# extension_card.net
KiCad netlist of a schematic drawn in Altium Designer
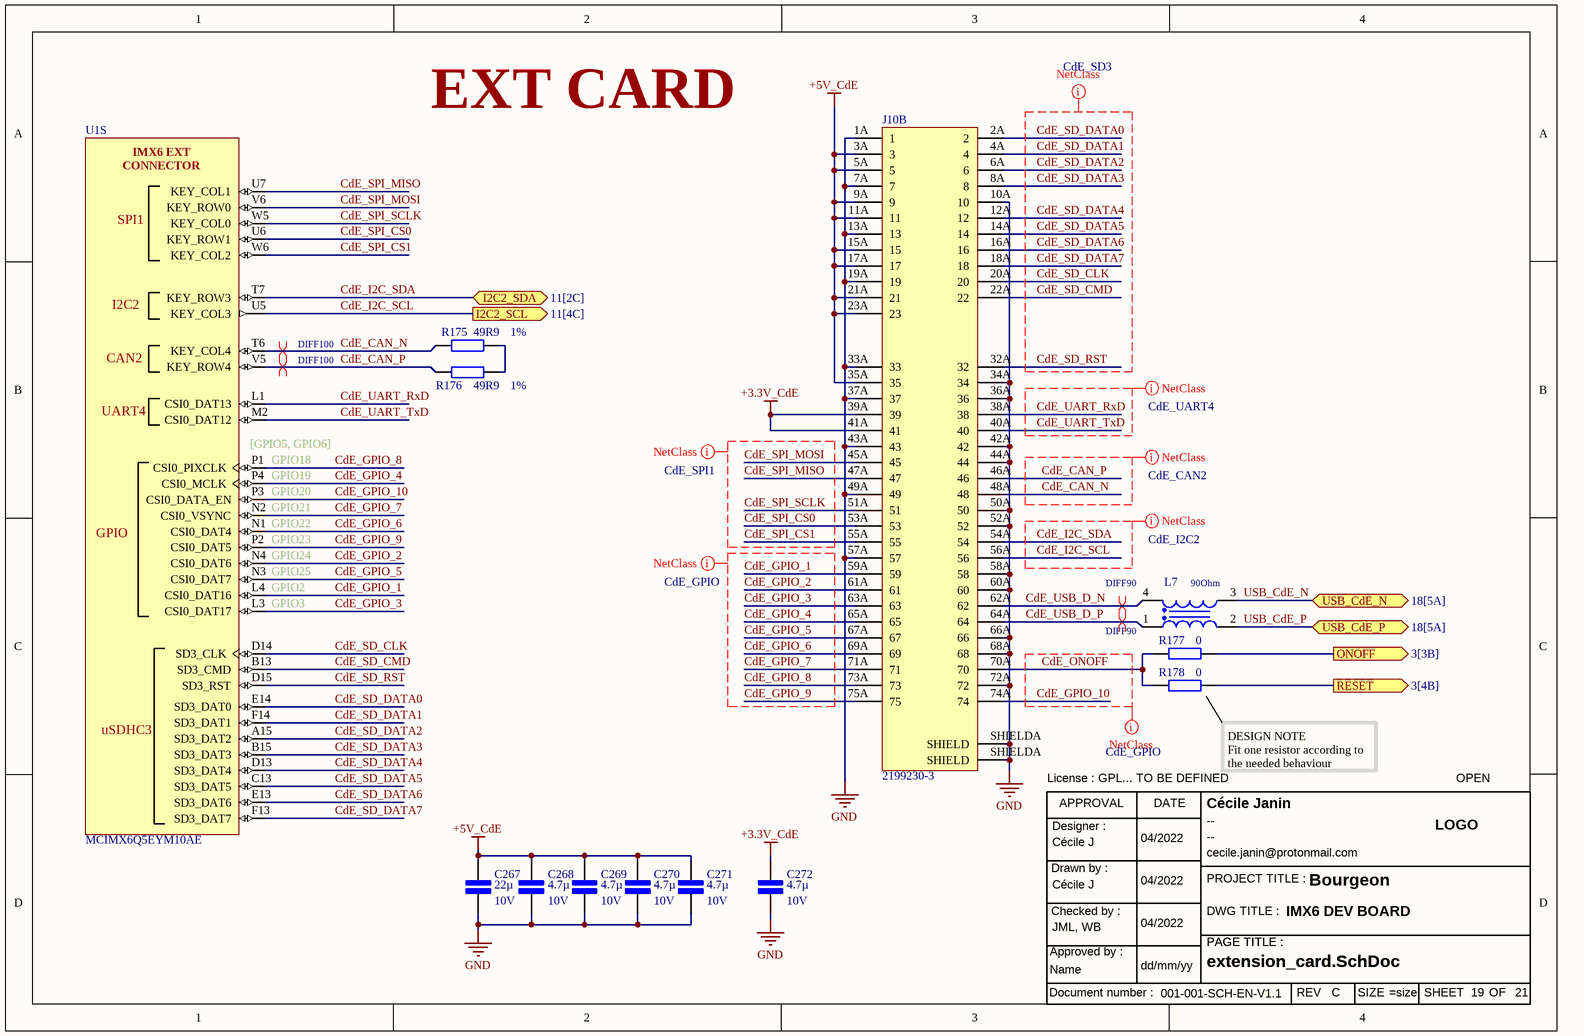
[diagram p0: extension_card.SchDoc]

(export (version "E")
  (design (tool "Eeschema 10.0.6"))
  (components
    (comp (ref "C267")
      (value "22µ")
      (footprint "Cap cer 0603/4608")
      (description "cap cer 22µ 10V 10% X5R 0603")
      (fields (field (name "TENSION DU DIÉLECTRIQUE") "10V"))
      (libsource (lib "First Board IMX6") (part "cap 22µ 10V"))
    )
    (comp (ref "C268")
      (value "4.7µ")
      (footprint "Cap cer 0402/1005")
      (description "cap cer 4.7µ 10V 10% X7R 0402")
      (fields (field (name "TENSION DU DIÉLECTRIQUE") "10V"))
      (libsource (lib "First Board IMX6") (part "cap 4.7µ 10V"))
    )
    (comp (ref "C269")
      (value "4.7µ")
      (footprint "Cap cer 0402/1005")
      (description "cap cer 4.7µ 10V 10% X7R 0402")
      (fields (field (name "TENSION DU DIÉLECTRIQUE") "10V"))
      (libsource (lib "First Board IMX6") (part "cap 4.7µ 10V"))
    )
    (comp (ref "C270")
      (value "4.7µ")
      (footprint "Cap cer 0402/1005")
      (description "cap cer 4.7µ 10V 10% X7R 0402")
      (fields (field (name "TENSION DU DIÉLECTRIQUE") "10V"))
      (libsource (lib "First Board IMX6") (part "cap 4.7µ 10V"))
    )
    (comp (ref "C271")
      (value "4.7µ")
      (footprint "Cap cer 0402/1005")
      (description "cap cer 4.7µ 10V 10% X7R 0402")
      (fields (field (name "TENSION DU DIÉLECTRIQUE") "10V"))
      (libsource (lib "First Board IMX6") (part "cap 4.7µ 10V"))
    )
    (comp (ref "C272")
      (value "4.7µ")
      (footprint "Cap cer 0402/1005")
      (description "cap cer 4.7µ 10V 10% X7R 0402")
      (fields (field (name "TENSION DU DIÉLECTRIQUE") "10V"))
      (libsource (lib "First Board IMX6") (part "cap 4.7µ 10V"))
    )
    (comp (ref "J10")
      (value "2199230-3")
      (footprint "SATA_M2_ 2199230-3")
      (libsource (lib "First Board IMX6") (part "SATA_M.2_2199230-3 / multi interface"))
    )
    (comp (ref "L7")
      (value "90Ohm")
      (footprint "inductor coupled usb 0603")
      (description "WE-CNSW SMT Common Mode Line Filter, size 0603, 90Ohm, 0.55A, 50V")
      (fields
        (field (name "MANUFACTURER PART NUMBER") "744230900")
        (field (name "MANUFACTURER") "Wurth Elektronik")
      )
      (libsource (lib "First Board IMX6") (part "inductor coupled USB"))
    )
    (comp (ref "R175")
      (value "49R9")
      (footprint "Res 0402/1005")
      (description "res 49R9 ohm 1% 0402")
      (fields (field (name "POURCENTAGE") "1%"))
      (libsource (lib "First Board IMX6") (part "res 49R9 1%"))
    )
    (comp (ref "R176")
      (value "49R9")
      (footprint "Res 0402/1005")
      (description "res 49R9 ohm 1% 0402")
      (fields (field (name "POURCENTAGE") "1%"))
      (libsource (lib "First Board IMX6") (part "res 49R9 1%"))
    )
    (comp (ref "R177")
      (value "0")
      (footprint "Res 0603/1603")
      (description "res 0603")
      (libsource (lib "First Board IMX6") (part "res 0Ohm"))
    )
    (comp (ref "R178")
      (value "0")
      (footprint "Res 0603/1603")
      (description "res 0603")
      (libsource (lib "First Board IMX6") (part "res 0Ohm"))
    )
    (comp (ref "TB18")
      (value "Title bloc ANSI modified")
      (libsource (lib "First Board IMX6") (part "Title bloc ANSI"))
    )
    (comp (ref "U1")
      (value "MCIMX6Q5EYM10AE")
      (footprint "FRES-2197-01")
      (fields
        (field (name "PARTNUMBER") "MCIMX6Q5EYM10ACR")
        (field (name "MANUFACTURER") "Freescale Semiconductor")
      )
      (libsource (lib "First Board IMX6") (part "IMX6Q5EYM10AE"))
    )
  )
  (nets
    (net (code "1") (name "+3.3V_CdE") (class "Default")
      (node (ref "C272") (pin "1") (pinfunction "3_1") (pintype "passive"))
      (node (ref "J10") (pin "39A") (pinfunction "39_39A") (pintype "passive"))
      (node (ref "J10") (pin "41A") (pinfunction "41_41A") (pintype "passive"))
    )
    (net (code "2") (name "+5V_CdE") (class "Default")
      (node (ref "C267") (pin "1") (pinfunction "3_1") (pintype "passive"))
      (node (ref "C268") (pin "1") (pinfunction "3_1") (pintype "passive"))
      (node (ref "C269") (pin "1") (pinfunction "3_1") (pintype "passive"))
      (node (ref "C270") (pin "1") (pinfunction "3_1") (pintype "passive"))
      (node (ref "C271") (pin "1") (pinfunction "3_1") (pintype "passive"))
      (node (ref "J10") (pin "11A") (pinfunction "11_11A") (pintype "passive"))
      (node (ref "J10") (pin "15A") (pinfunction "15_15A") (pintype "passive"))
      (node (ref "J10") (pin "17A") (pinfunction "17_17A") (pintype "passive"))
      (node (ref "J10") (pin "21A") (pinfunction "21_21A") (pintype "passive"))
      (node (ref "J10") (pin "23A") (pinfunction "23_23A") (pintype "passive"))
      (node (ref "J10") (pin "35A") (pinfunction "35_35A") (pintype "passive"))
      (node (ref "J10") (pin "3A") (pinfunction "3_3A") (pintype "passive"))
      (node (ref "J10") (pin "5A") (pinfunction "5_5A") (pintype "passive"))
      (node (ref "J10") (pin "9A") (pinfunction "9_9A") (pintype "passive"))
    )
    (net (code "3") (name "/CdE_CAN_N") (class "Default")
      (node (ref "J10") (pin "48A") (pinfunction "48_48A") (pintype "passive"))
      (node (ref "R175") (pin "2") (pintype "passive"))
      (node (ref "U1") (pin "T6") (pinfunction "KEY_COL4_T6") (pintype "bidirectional"))
    )
    (net (code "4") (name "/CdE_CAN_P") (class "Default")
      (node (ref "J10") (pin "46A") (pinfunction "46_46A") (pintype "passive"))
      (node (ref "R176") (pin "2") (pintype "passive"))
      (node (ref "U1") (pin "V5") (pinfunction "KEY_ROW4_V5") (pintype "bidirectional"))
    )
    (net (code "5") (name "/CdE_GPIO_1") (class "Default")
      (node (ref "J10") (pin "59A") (pinfunction "59_59A") (pintype "passive"))
      (node (ref "U1") (pin "L4") (pinfunction "CSI0_DAT16_L4") (pintype "bidirectional"))
    )
    (net (code "6") (name "/CdE_GPIO_2") (class "Default")
      (node (ref "J10") (pin "61A") (pinfunction "61_61A") (pintype "passive"))
      (node (ref "U1") (pin "N4") (pinfunction "CSI0_DAT6_N4") (pintype "bidirectional"))
    )
    (net (code "7") (name "/CdE_GPIO_3") (class "Default")
      (node (ref "J10") (pin "63A") (pinfunction "63_63A") (pintype "passive"))
      (node (ref "U1") (pin "L3") (pinfunction "CSI0_DAT17_L3") (pintype "bidirectional"))
    )
    (net (code "8") (name "/CdE_GPIO_4") (class "Default")
      (node (ref "J10") (pin "65A") (pinfunction "65_65A") (pintype "passive"))
      (node (ref "U1") (pin "P4") (pinfunction "CSI0_MCLK_P4") (pintype "bidirectional"))
    )
    (net (code "9") (name "/CdE_GPIO_5") (class "Default")
      (node (ref "J10") (pin "67A") (pinfunction "67_67A") (pintype "passive"))
      (node (ref "U1") (pin "N3") (pinfunction "CSI0_DAT7_N3") (pintype "bidirectional"))
    )
    (net (code "10") (name "/CdE_GPIO_6") (class "Default")
      (node (ref "J10") (pin "69A") (pinfunction "69_69A") (pintype "passive"))
      (node (ref "U1") (pin "N1") (pinfunction "CSI0_DAT4_N1") (pintype "bidirectional"))
    )
    (net (code "11") (name "/CdE_GPIO_7") (class "Default")
      (node (ref "J10") (pin "71A") (pinfunction "71_71A") (pintype "passive"))
      (node (ref "U1") (pin "N2") (pinfunction "CSI0_VSYNC_N2") (pintype "bidirectional"))
    )
    (net (code "12") (name "/CdE_GPIO_8") (class "Default")
      (node (ref "J10") (pin "73A") (pinfunction "73_73A") (pintype "passive"))
      (node (ref "U1") (pin "P1") (pinfunction "CSI0_PIXCLK_P1") (pintype "bidirectional"))
    )
    (net (code "13") (name "/CdE_GPIO_9") (class "Default")
      (node (ref "J10") (pin "75A") (pinfunction "75_75A") (pintype "passive"))
      (node (ref "U1") (pin "P2") (pinfunction "CSI0_DAT5_P2") (pintype "bidirectional"))
    )
    (net (code "14") (name "/CdE_GPIO_10") (class "Default")
      (node (ref "J10") (pin "74A") (pinfunction "74_74A") (pintype "passive"))
      (node (ref "U1") (pin "P3") (pinfunction "CSI0_DATA_EN_P3") (pintype "bidirectional"))
    )
    (net (code "15") (name "/CdE_I2C_SCL") (class "Default")
      (node (ref "J10") (pin "56A") (pinfunction "56_56A") (pintype "passive"))
      (node (ref "U1") (pin "U5") (pinfunction "KEY_COL3_U5") (pintype "output"))
    )
    (net (code "16") (name "/CdE_I2C_SDA") (class "Default")
      (node (ref "J10") (pin "54A") (pinfunction "54_54A") (pintype "passive"))
      (node (ref "U1") (pin "T7") (pinfunction "KEY_ROW3_T7") (pintype "bidirectional"))
    )
    (net (code "17") (name "/CdE_ONOFF") (class "Default")
      (node (ref "J10") (pin "70A") (pinfunction "70_70A") (pintype "passive"))
      (node (ref "R177") (pin "1") (pintype "passive"))
      (node (ref "R178") (pin "1") (pintype "passive"))
    )
    (net (code "18") (name "/CdE_SD_CLK") (class "Default")
      (node (ref "J10") (pin "20A") (pinfunction "20_20A") (pintype "passive"))
      (node (ref "U1") (pin "D14") (pinfunction "SD3_CLK_D14") (pintype "bidirectional"))
    )
    (net (code "19") (name "/CdE_SD_CMD") (class "Default")
      (node (ref "J10") (pin "22A") (pinfunction "22_22A") (pintype "passive"))
      (node (ref "U1") (pin "B13") (pinfunction "SD3_CMD_B13") (pintype "bidirectional"))
    )
    (net (code "20") (name "/CdE_SD_DATA0") (class "Default")
      (node (ref "J10") (pin "2A") (pinfunction "2_2A") (pintype "passive"))
      (node (ref "U1") (pin "E14") (pinfunction "SD3_DAT0_E14") (pintype "bidirectional"))
    )
    (net (code "21") (name "/CdE_SD_DATA1") (class "Default")
      (node (ref "J10") (pin "4A") (pinfunction "4_4A") (pintype "passive"))
      (node (ref "U1") (pin "F14") (pinfunction "SD3_DAT1_F14") (pintype "bidirectional"))
    )
    (net (code "22") (name "/CdE_SD_DATA2") (class "Default")
      (node (ref "J10") (pin "6A") (pinfunction "6_6A") (pintype "passive"))
      (node (ref "U1") (pin "A15") (pinfunction "SD3_DAT2_A15") (pintype "bidirectional"))
    )
    (net (code "23") (name "/CdE_SD_DATA3") (class "Default")
      (node (ref "J10") (pin "8A") (pinfunction "8_8A") (pintype "passive"))
      (node (ref "U1") (pin "B15") (pinfunction "SD3_DAT3_B15") (pintype "bidirectional"))
    )
    (net (code "24") (name "/CdE_SD_DATA4") (class "Default")
      (node (ref "J10") (pin "12A") (pinfunction "12_12A") (pintype "passive"))
      (node (ref "U1") (pin "D13") (pinfunction "SD3_DAT4_D13") (pintype "bidirectional"))
    )
    (net (code "25") (name "/CdE_SD_DATA5") (class "Default")
      (node (ref "J10") (pin "14A") (pinfunction "14_14A") (pintype "passive"))
      (node (ref "U1") (pin "C13") (pinfunction "SD3_DAT5_C13") (pintype "bidirectional"))
    )
    (net (code "26") (name "/CdE_SD_DATA6") (class "Default")
      (node (ref "J10") (pin "16A") (pinfunction "16_16A") (pintype "passive"))
      (node (ref "U1") (pin "E13") (pinfunction "SD3_DAT6_E13") (pintype "bidirectional"))
    )
    (net (code "27") (name "/CdE_SD_DATA7") (class "Default")
      (node (ref "J10") (pin "18A") (pinfunction "18_18A") (pintype "passive"))
      (node (ref "U1") (pin "F13") (pinfunction "SD3_DAT7_F13") (pintype "bidirectional"))
    )
    (net (code "28") (name "/CdE_SD_RST") (class "Default")
      (node (ref "J10") (pin "32A") (pinfunction "32_32A") (pintype "passive"))
      (node (ref "U1") (pin "D15") (pinfunction "SD3_RST_D15") (pintype "bidirectional"))
    )
    (net (code "29") (name "/CdE_SPI_CS0") (class "Default")
      (node (ref "J10") (pin "53A") (pinfunction "53_53A") (pintype "passive"))
      (node (ref "U1") (pin "U6") (pinfunction "KEY_ROW1_U6") (pintype "bidirectional"))
    )
    (net (code "30") (name "/CdE_SPI_CS1") (class "Default")
      (node (ref "J10") (pin "55A") (pinfunction "55_55A") (pintype "passive"))
      (node (ref "U1") (pin "W6") (pinfunction "KEY_COL2_W6") (pintype "bidirectional"))
    )
    (net (code "31") (name "/CdE_SPI_MISO") (class "Default")
      (node (ref "J10") (pin "47A") (pinfunction "47_47A") (pintype "passive"))
      (node (ref "U1") (pin "U7") (pinfunction "KEY_COL1_U7") (pintype "bidirectional"))
    )
    (net (code "32") (name "/CdE_SPI_MOSI") (class "Default")
      (node (ref "J10") (pin "45A") (pinfunction "45_45A") (pintype "passive"))
      (node (ref "U1") (pin "V6") (pinfunction "KEY_ROW0_V6") (pintype "bidirectional"))
    )
    (net (code "33") (name "/CdE_SPI_SCLK") (class "Default")
      (node (ref "J10") (pin "51A") (pinfunction "51_51A") (pintype "passive"))
      (node (ref "U1") (pin "W5") (pinfunction "KEY_COL0_W5") (pintype "bidirectional"))
    )
    (net (code "34") (name "/CdE_UART_RxD") (class "Default")
      (node (ref "J10") (pin "38A") (pinfunction "38_38A") (pintype "passive"))
      (node (ref "U1") (pin "L1") (pinfunction "CSI0_DAT13_L1") (pintype "bidirectional"))
    )
    (net (code "35") (name "/CdE_UART_TxD") (class "Default")
      (node (ref "J10") (pin "40A") (pinfunction "40_40A") (pintype "passive"))
      (node (ref "U1") (pin "M2") (pinfunction "CSI0_DAT12_M2") (pintype "bidirectional"))
    )
    (net (code "36") (name "/CdE_USB_D_N") (class "Default")
      (node (ref "J10") (pin "62A") (pinfunction "62_62A") (pintype "passive"))
      (node (ref "L7") (pin "4") (pinfunction "4_4") (pintype "passive"))
    )
    (net (code "37") (name "/CdE_USB_D_P") (class "Default")
      (node (ref "J10") (pin "64A") (pinfunction "64_64A") (pintype "passive"))
      (node (ref "L7") (pin "1") (pinfunction "1_1") (pintype "passive"))
    )
    (net (code "38") (name "/ONOFF") (class "Default") (node (ref "R177") (pin "2") (pintype "passive")))
    (net (code "39") (name "/RESET") (class "Default") (node (ref "R178") (pin "2") (pintype "passive")))
    (net (code "40") (name "/USB_CdE_N") (class "Default")
      (node (ref "L7") (pin "3") (pinfunction "3_3") (pintype "passive"))
    )
    (net (code "41") (name "/USB_CdE_P") (class "Default")
      (node (ref "L7") (pin "2") (pinfunction "2_2") (pintype "passive"))
    )
    (net (code "42") (name "GND") (class "Default")
      (node (ref "C267") (pin "2") (pinfunction "4_2") (pintype "passive"))
      (node (ref "C268") (pin "2") (pinfunction "4_2") (pintype "passive"))
      (node (ref "C269") (pin "2") (pinfunction "4_2") (pintype "passive"))
      (node (ref "C270") (pin "2") (pinfunction "4_2") (pintype "passive"))
      (node (ref "C271") (pin "2") (pinfunction "4_2") (pintype "passive"))
      (node (ref "C272") (pin "2") (pinfunction "4_2") (pintype "passive"))
      (node (ref "J10") (pin "10A") (pinfunction "10_10A") (pintype "passive"))
      (node (ref "J10") (pin "13A") (pinfunction "13_13A") (pintype "passive"))
      (node (ref "J10") (pin "19A") (pinfunction "19_19A") (pintype "passive"))
      (node (ref "J10") (pin "1A") (pinfunction "1_1A") (pintype "passive"))
      (node (ref "J10") (pin "33A") (pinfunction "33_33A") (pintype "passive"))
      (node (ref "J10") (pin "34A") (pinfunction "34_34A") (pintype "passive"))
      (node (ref "J10") (pin "36A") (pinfunction "36_36A") (pintype "passive"))
      (node (ref "J10") (pin "37A") (pinfunction "37_37A") (pintype "passive"))
      (node (ref "J10") (pin "42A") (pinfunction "42_42A") (pintype "passive"))
      (node (ref "J10") (pin "43A") (pinfunction "43_43A") (pintype "passive"))
      (node (ref "J10") (pin "44A") (pinfunction "44_44A") (pintype "passive"))
      (node (ref "J10") (pin "49A") (pinfunction "49_49A") (pintype "passive"))
      (node (ref "J10") (pin "50A") (pinfunction "50_50A") (pintype "passive"))
      (node (ref "J10") (pin "52A") (pinfunction "52_52A") (pintype "passive"))
      (node (ref "J10") (pin "57A") (pinfunction "57_57A") (pintype "passive"))
      (node (ref "J10") (pin "58A") (pinfunction "58_58A") (pintype "passive"))
      (node (ref "J10") (pin "60A") (pinfunction "60_60A") (pintype "passive"))
      (node (ref "J10") (pin "66A") (pinfunction "66_66A") (pintype "passive"))
      (node (ref "J10") (pin "68A") (pinfunction "68_68A") (pintype "passive"))
      (node (ref "J10") (pin "72A") (pinfunction "72_72A") (pintype "passive"))
      (node (ref "J10") (pin "7A") (pinfunction "7_7A") (pintype "passive"))
      (node (ref "J10") (pin "SHIELDA") (pinfunction "SHIELD_SHIELDA") (pintype "passive"))
    )
    (net (code "43") (name "Net-(R175-Pad1)") (class "Default")
      (node (ref "R175") (pin "1") (pintype "passive"))
      (node (ref "R176") (pin "1") (pintype "passive"))
    )
  )
)
